# STM32F103C8T6_Minimum_system.net
KiCad netlist of a schematic drawn in Altium Designer
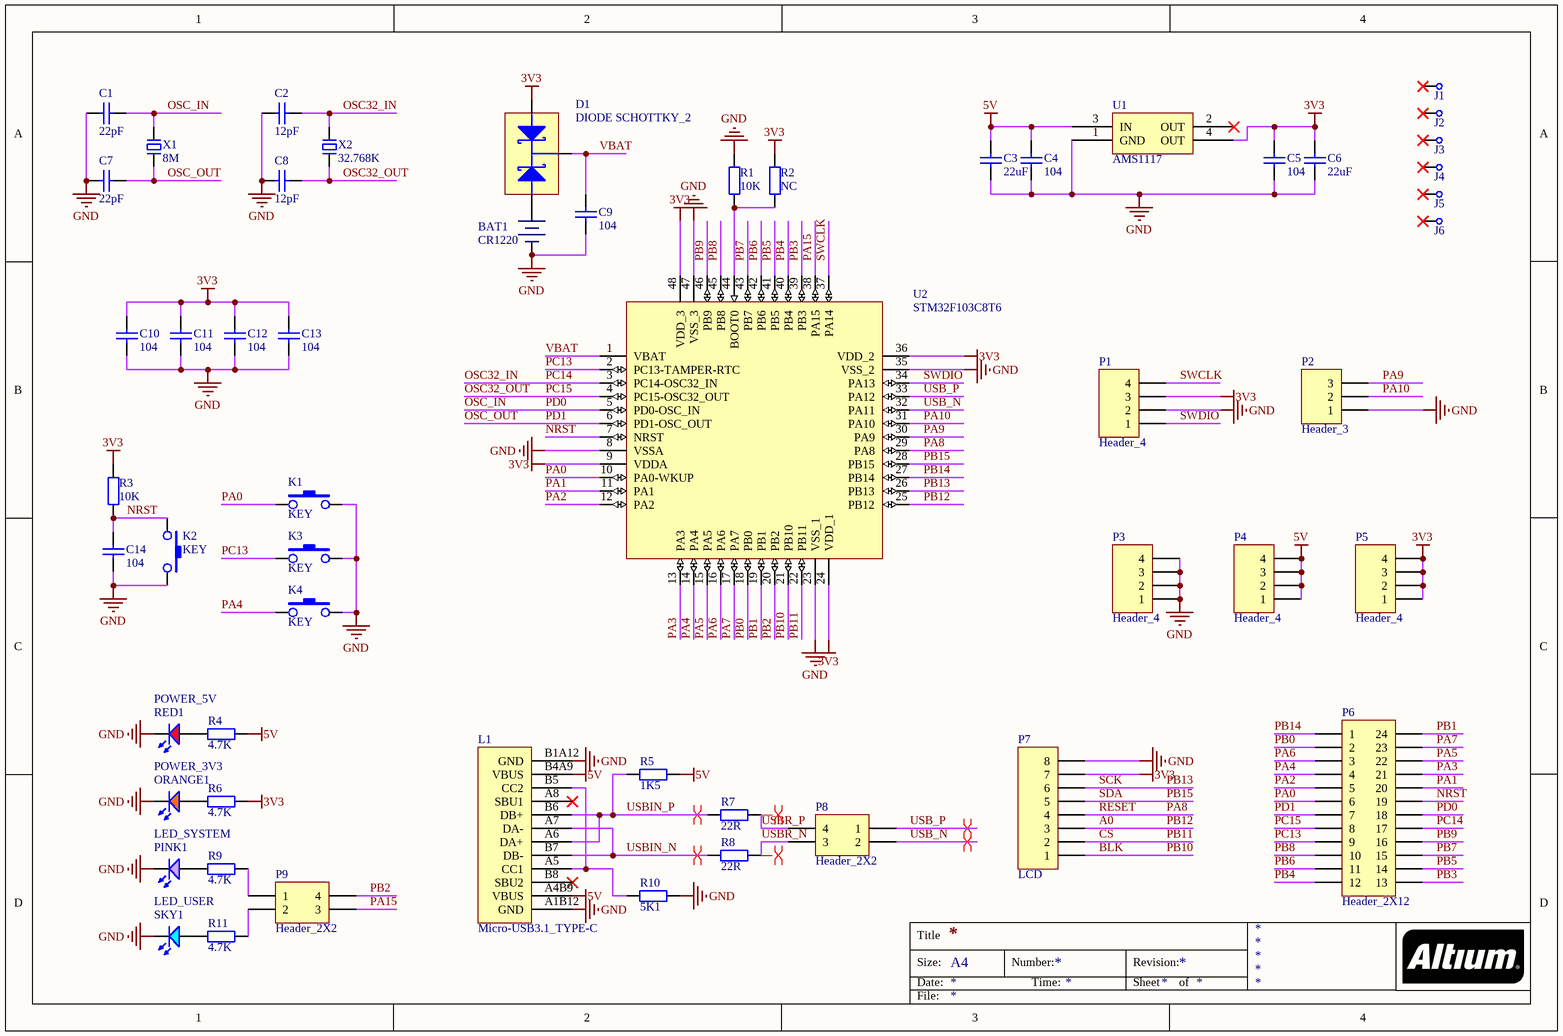
[diagram p0: STM32F103C8T6 Minimum system.SchDoc]

(export (version "E")
  (design (tool "Eeschema 10.0.6"))
  (components
    (comp (ref "BAT1")
      (value "CR1220")
      (footprint "CR1220-B")
      (description "纽扣电池座")
      (libsource (lib "Miscellaneous Socket") (part "CR1220"))
    )
    (comp (ref "C1")
      (value "22pF")
      (footprint "Cap-0603")
      (description "贴片陶瓷电容")
      (libsource (lib "Miscellaneous Base") (part "CAP"))
    )
    (comp (ref "C2")
      (value "12pF")
      (footprint "Cap-0603")
      (description "贴片陶瓷电容")
      (libsource (lib "Miscellaneous Base") (part "CAP"))
    )
    (comp (ref "C3")
      (value "22uF")
      (footprint "Cap-0805")
      (description "贴片陶瓷电容")
      (libsource (lib "Miscellaneous Base") (part "CAP"))
    )
    (comp (ref "C4")
      (value "104")
      (footprint "Cap-0603")
      (description "贴片陶瓷电容")
      (libsource (lib "Miscellaneous Base") (part "CAP"))
    )
    (comp (ref "C5")
      (value "104")
      (footprint "Cap-0603")
      (description "贴片陶瓷电容")
      (libsource (lib "Miscellaneous Base") (part "CAP"))
    )
    (comp (ref "C6")
      (value "22uF")
      (footprint "Cap-0805")
      (description "贴片陶瓷电容")
      (libsource (lib "Miscellaneous Base") (part "CAP"))
    )
    (comp (ref "C7")
      (value "22pF")
      (footprint "Cap-0603")
      (description "贴片陶瓷电容")
      (libsource (lib "Miscellaneous Base") (part "CAP"))
    )
    (comp (ref "C8")
      (value "12pF")
      (footprint "Cap-0603")
      (description "贴片陶瓷电容")
      (libsource (lib "Miscellaneous Base") (part "CAP"))
    )
    (comp (ref "C9")
      (value "104")
      (footprint "Cap-0603")
      (description "贴片陶瓷电容")
      (libsource (lib "Miscellaneous Base") (part "CAP"))
    )
    (comp (ref "C10")
      (value "104")
      (footprint "Cap-0603")
      (description "贴片陶瓷电容")
      (libsource (lib "Miscellaneous Base") (part "CAP"))
    )
    (comp (ref "C11")
      (value "104")
      (footprint "Cap-0603")
      (description "贴片陶瓷电容")
      (libsource (lib "Miscellaneous Base") (part "CAP"))
    )
    (comp (ref "C12")
      (value "104")
      (footprint "Cap-0603")
      (description "贴片陶瓷电容")
      (libsource (lib "Miscellaneous Base") (part "CAP"))
    )
    (comp (ref "C13")
      (value "104")
      (footprint "Cap-0603")
      (description "贴片陶瓷电容")
      (libsource (lib "Miscellaneous Base") (part "CAP"))
    )
    (comp (ref "C14")
      (value "104")
      (footprint "Cap-0603")
      (description "贴片陶瓷电容")
      (libsource (lib "Miscellaneous Base") (part "CAP"))
    )
    (comp (ref "D1")
      (value "DIODE SCHOTTKY_2")
      (footprint "SOT23-3")
      (description "双肖特基二极管")
      (libsource (lib "Miscellaneous Transistor") (part "DIODE SCHOTTKY_2"))
    )
    (comp (ref "J1")
      (value "HOLE_2mm")
      (footprint "HOLE_2mm_1")
      (description "定位孔")
      (libsource (lib "Miscellaneous Others") (part "HOLE_2mm"))
    )
    (comp (ref "J2")
      (value "HOLE_2mm")
      (footprint "HOLE_2mm_1")
      (description "定位孔")
      (libsource (lib "Miscellaneous Others") (part "HOLE_2mm"))
    )
    (comp (ref "J3")
      (value "HOLE_2mm")
      (footprint "HOLE_2mm_1")
      (description "定位孔")
      (libsource (lib "Miscellaneous Others") (part "HOLE_2mm"))
    )
    (comp (ref "J4")
      (value "HOLE_2mm")
      (footprint "HOLE_2mm_1")
      (description "定位孔")
      (libsource (lib "Miscellaneous Others") (part "HOLE_2mm"))
    )
    (comp (ref "J5")
      (value "HOLE_2mm")
      (footprint "HOLE_2mm_1")
      (description "定位孔")
      (libsource (lib "Miscellaneous Others") (part "HOLE_2mm"))
    )
    (comp (ref "J6")
      (value "HOLE_2mm")
      (footprint "HOLE_2mm_1")
      (description "定位孔")
      (libsource (lib "Miscellaneous Others") (part "HOLE_2mm"))
    )
    (comp (ref "K1")
      (value "KEY")
      (footprint "SW-SMD-3X4X2.5")
      (libsource (lib "Miscellaneous Switch") (part "KEY"))
    )
    (comp (ref "K2")
      (value "KEY")
      (footprint "SW-SMD-3X4X2.5")
      (libsource (lib "Miscellaneous Switch") (part "KEY"))
    )
    (comp (ref "K3")
      (value "KEY")
      (footprint "SW-SMD-3X4X2.5")
      (libsource (lib "Miscellaneous Switch") (part "KEY"))
    )
    (comp (ref "K4")
      (value "KEY")
      (footprint "SW-SMD-3X4X2.5")
      (libsource (lib "Miscellaneous Switch") (part "KEY"))
    )
    (comp (ref "L1")
      (value "Micro-USB3.1_TYPE-C")
      (footprint "USB3.0-TYPEC-12P")
      (libsource (lib "Miscellaneous Socket") (part "Micro-USB3.1_TYPE-C"))
    )
    (comp (ref "ORANGE1")
      (value "POWER_3V3")
      (footprint "LED_0603_Y")
      (description "发光二极管")
      (libsource (lib "Miscellaneous Transistor") (part "LED_SMD_ORANGE"))
    )
    (comp (ref "P1")
      (value "Header_4")
      (footprint "Header 2.54X4")
      (libsource (lib "Miscellaneous Header") (part "Header_4"))
    )
    (comp (ref "P2")
      (value "Header_3")
      (footprint "Header 2.54X3")
      (libsource (lib "Miscellaneous Header") (part "Header_3"))
    )
    (comp (ref "P3")
      (value "Header_4")
      (footprint "Header 2.54X4")
      (libsource (lib "Miscellaneous Header") (part "Header_4"))
    )
    (comp (ref "P4")
      (value "Header_4")
      (footprint "Header 2.54X4")
      (libsource (lib "Miscellaneous Header") (part "Header_4"))
    )
    (comp (ref "P5")
      (value "Header_4")
      (footprint "Header 2.54X4")
      (libsource (lib "Miscellaneous Header") (part "Header_4"))
    )
    (comp (ref "P6")
      (value "Header_2X12")
      (footprint "Header 2.54_2X12")
      (libsource (lib "Miscellaneous Header") (part "Header_2X12"))
    )
    (comp (ref "P7")
      (value "LCD")
      (footprint "Header 2.54X8")
      (libsource (lib "Miscellaneous Header") (part "Header_8"))
    )
    (comp (ref "P8")
      (value "Header_2X2")
      (footprint "Header 2.54_2X2")
      (libsource (lib "Miscellaneous Header") (part "Header_2X2"))
    )
    (comp (ref "P9")
      (value "Header_2X2")
      (footprint "Header 2.54_2X2")
      (libsource (lib "") (part "Header_2X2_1"))
    )
    (comp (ref "PINK1")
      (value "LED_SYSTEM")
      (footprint "LED_0603_R")
      (description "发光二极管")
      (libsource (lib "Miscellaneous Transistor") (part "LED_SMD_PINK"))
    )
    (comp (ref "R1")
      (value "10K")
      (footprint "Res-0603")
      (description "贴片电阻")
      (libsource (lib "Miscellaneous Base") (part "RES"))
    )
    (comp (ref "R2")
      (value "NC")
      (footprint "Res-0603")
      (description "贴片电阻")
      (libsource (lib "Miscellaneous Base") (part "RES"))
    )
    (comp (ref "R3")
      (value "10K")
      (footprint "Res-0603")
      (description "贴片电阻")
      (libsource (lib "Miscellaneous Base") (part "RES"))
    )
    (comp (ref "R4")
      (value "4.7K")
      (footprint "Res-0603")
      (description "贴片电阻")
      (libsource (lib "") (part "RES_1"))
    )
    (comp (ref "R5")
      (value "1K5")
      (footprint "Res-0603")
      (description "贴片电阻")
      (libsource (lib "") (part "RES_2"))
    )
    (comp (ref "R6")
      (value "4.7K")
      (footprint "Res-0603")
      (description "贴片电阻")
      (libsource (lib "") (part "RES_1"))
    )
    (comp (ref "R7")
      (value "22R")
      (footprint "Res-0603")
      (description "贴片电阻")
      (libsource (lib "") (part "RES_2"))
    )
    (comp (ref "R8")
      (value "22R")
      (footprint "Res-0603")
      (description "贴片电阻")
      (libsource (lib "") (part "RES_2"))
    )
    (comp (ref "R9")
      (value "4.7K")
      (footprint "Res-0603")
      (description "贴片电阻")
      (libsource (lib "") (part "RES_1"))
    )
    (comp (ref "R10")
      (value "5K1")
      (footprint "Res-0603")
      (description "贴片电阻")
      (libsource (lib "") (part "RES_2"))
    )
    (comp (ref "R11")
      (value "4.7K")
      (footprint "Res-0603")
      (description "贴片电阻")
      (libsource (lib "") (part "RES_1"))
    )
    (comp (ref "RED1")
      (value "POWER_5V")
      (footprint "LED_0603_R")
      (description "发光二极管")
      (libsource (lib "Miscellaneous Transistor") (part "LED_SMD_RED"))
    )
    (comp (ref "SKY1")
      (value "LED_USER")
      (footprint "LED_0603_B")
      (description "发光二极管")
      (libsource (lib "Miscellaneous Transistor") (part "LED_SMD_BLUE_SKY"))
    )
    (comp (ref "U1")
      (value "AMS1117")
      (footprint "AMS1117")
      (libsource (lib "Miscellaneous PMIC") (part "AMS1117"))
    )
    (comp (ref "U2")
      (value "STM32F103C8T6")
      (footprint "STM32F103C8T6")
      (libsource (lib "Miscellaneous MCU") (part "STM32F103C8T6"))
    )
    (comp (ref "X1")
      (value "8M")
      (footprint "OSC 5032-2P")
      (description "2脚无源脚晶振")
      (libsource (lib "Miscellaneous XTAL") (part "XTAL-2P"))
    )
    (comp (ref "X2")
      (value "32.768K")
      (footprint "OSC 3215-2P")
      (description "2脚无源脚晶振")
      (libsource (lib "Miscellaneous XTAL") (part "XTAL-2P"))
    )
  )
  (nets
    (net (code "1") (name "/A0") (class "Default")
      (node (ref "P7") (pin "3") (pinfunction "3_3") (pintype "passive"))
      (node (ref "U2") (pin "25") (pinfunction "PB12_25") (pintype "bidirectional"))
    )
    (net (code "2") (name "/BLK") (class "Default")
      (node (ref "P7") (pin "1") (pinfunction "1_1") (pintype "passive"))
      (node (ref "U2") (pin "21") (pinfunction "PB10_21") (pintype "bidirectional"))
    )
    (net (code "3") (name "/CS") (class "Default")
      (node (ref "P7") (pin "2") (pinfunction "2_2") (pintype "passive"))
      (node (ref "U2") (pin "22") (pinfunction "PB11_22") (pintype "bidirectional"))
    )
    (net (code "4") (name "/NRST") (class "Default")
      (node (ref "C14") (pin "2") (pinfunction "2_2") (pintype "passive"))
      (node (ref "K2") (pin "1") (pinfunction "1_1") (pintype "passive"))
      (node (ref "P6") (pin "19") (pinfunction "19_19") (pintype "power_in"))
      (node (ref "R3") (pin "1") (pinfunction "1_1") (pintype "passive"))
      (node (ref "U2") (pin "7") (pinfunction "NRST_7") (pintype "bidirectional"))
    )
    (net (code "5") (name "/OSC32_IN") (class "Default")
      (node (ref "C2") (pin "2") (pinfunction "2_2") (pintype "passive"))
      (node (ref "P6") (pin "17") (pinfunction "17_17") (pintype "power_in"))
      (node (ref "U2") (pin "3") (pinfunction "PC14-OSC32_IN_3") (pintype "bidirectional"))
      (node (ref "X2") (pin "2") (pinfunction "2_2") (pintype "passive"))
    )
    (net (code "6") (name "/OSC32_OUT") (class "Default")
      (node (ref "C8") (pin "2") (pinfunction "2_2") (pintype "passive"))
      (node (ref "P6") (pin "8") (pinfunction "8_8") (pintype "power_in"))
      (node (ref "U2") (pin "4") (pinfunction "PC15-OSC32_OUT_4") (pintype "bidirectional"))
      (node (ref "X2") (pin "1") (pinfunction "1_1") (pintype "passive"))
    )
    (net (code "7") (name "/OSC_IN") (class "Default")
      (node (ref "C1") (pin "2") (pinfunction "2_2") (pintype "passive"))
      (node (ref "P6") (pin "18") (pinfunction "18_18") (pintype "power_in"))
      (node (ref "U2") (pin "5") (pinfunction "PD0-OSC_IN_5") (pintype "bidirectional"))
      (node (ref "X1") (pin "2") (pinfunction "2_2") (pintype "passive"))
    )
    (net (code "8") (name "/OSC_OUT") (class "Default")
      (node (ref "C7") (pin "2") (pinfunction "2_2") (pintype "passive"))
      (node (ref "P6") (pin "7") (pinfunction "7_7") (pintype "power_in"))
      (node (ref "U2") (pin "6") (pinfunction "PD1-OSC_OUT_6") (pintype "bidirectional"))
      (node (ref "X1") (pin "1") (pinfunction "1_1") (pintype "passive"))
    )
    (net (code "9") (name "/PA0") (class "Default")
      (node (ref "K1") (pin "1") (pinfunction "1_1") (pintype "passive"))
      (node (ref "P6") (pin "6") (pinfunction "6_6") (pintype "power_in"))
      (node (ref "U2") (pin "10") (pinfunction "PA0-WKUP_10") (pintype "bidirectional"))
    )
    (net (code "10") (name "/PA1") (class "Default")
      (node (ref "P6") (pin "20") (pinfunction "20_20") (pintype "power_in"))
      (node (ref "U2") (pin "11") (pinfunction "PA1_11") (pintype "bidirectional"))
    )
    (net (code "11") (name "/PA2") (class "Default")
      (node (ref "P6") (pin "5") (pinfunction "5_5") (pintype "power_in"))
      (node (ref "U2") (pin "12") (pinfunction "PA2_12") (pintype "bidirectional"))
    )
    (net (code "12") (name "/PA3") (class "Default")
      (node (ref "P6") (pin "21") (pinfunction "21_21") (pintype "power_in"))
      (node (ref "U2") (pin "13") (pinfunction "PA3_13") (pintype "bidirectional"))
    )
    (net (code "13") (name "/PA4") (class "Default")
      (node (ref "K4") (pin "1") (pinfunction "1_1") (pintype "passive"))
      (node (ref "P6") (pin "4") (pinfunction "4_4") (pintype "power_in"))
      (node (ref "U2") (pin "14") (pinfunction "PA4_14") (pintype "bidirectional"))
    )
    (net (code "14") (name "/PA5") (class "Default")
      (node (ref "P6") (pin "22") (pinfunction "22_22") (pintype "power_in"))
      (node (ref "U2") (pin "15") (pinfunction "PA5_15") (pintype "bidirectional"))
    )
    (net (code "15") (name "/PA6") (class "Default")
      (node (ref "P6") (pin "3") (pinfunction "3_3") (pintype "power_in"))
      (node (ref "U2") (pin "16") (pinfunction "PA6_16") (pintype "bidirectional"))
    )
    (net (code "16") (name "/PA7") (class "Default")
      (node (ref "P6") (pin "23") (pinfunction "23_23") (pintype "power_in"))
      (node (ref "U2") (pin "17") (pinfunction "PA7_17") (pintype "bidirectional"))
    )
    (net (code "17") (name "/PA8") (class "Default")
      (node (ref "P7") (pin "4") (pinfunction "4_4") (pintype "passive"))
      (node (ref "U2") (pin "29") (pinfunction "PA8_29") (pintype "bidirectional"))
    )
    (net (code "18") (name "/PA9") (class "Default")
      (node (ref "P2") (pin "3") (pinfunction "3_3") (pintype "passive"))
      (node (ref "U2") (pin "30") (pinfunction "PA9_30") (pintype "bidirectional"))
    )
    (net (code "19") (name "/PA10") (class "Default")
      (node (ref "P2") (pin "2") (pinfunction "2_2") (pintype "passive"))
      (node (ref "U2") (pin "31") (pinfunction "PA10_31") (pintype "bidirectional"))
    )
    (net (code "20") (name "/PA15") (class "Default")
      (node (ref "P9") (pin "3") (pinfunction "3_3") (pintype "passive"))
      (node (ref "U2") (pin "38") (pinfunction "PA15_38") (pintype "bidirectional"))
    )
    (net (code "21") (name "/PB0") (class "Default")
      (node (ref "P6") (pin "2") (pinfunction "2_2") (pintype "power_in"))
      (node (ref "U2") (pin "18") (pinfunction "PB0_18") (pintype "bidirectional"))
    )
    (net (code "22") (name "/PB1") (class "Default")
      (node (ref "P6") (pin "24") (pinfunction "24_24") (pintype "power_in"))
      (node (ref "U2") (pin "19") (pinfunction "PB1_19") (pintype "bidirectional"))
    )
    (net (code "23") (name "/PB2") (class "Default")
      (node (ref "P9") (pin "4") (pinfunction "4_4") (pintype "passive"))
      (node (ref "U2") (pin "20") (pinfunction "PB2_20") (pintype "bidirectional"))
    )
    (net (code "24") (name "/PB3") (class "Default")
      (node (ref "P6") (pin "13") (pinfunction "13_13") (pintype "power_in"))
      (node (ref "U2") (pin "39") (pinfunction "PB3_39") (pintype "bidirectional"))
    )
    (net (code "25") (name "/PB4") (class "Default")
      (node (ref "P6") (pin "12") (pinfunction "12_12") (pintype "power_in"))
      (node (ref "U2") (pin "40") (pinfunction "PB4_40") (pintype "bidirectional"))
    )
    (net (code "26") (name "/PB5") (class "Default")
      (node (ref "P6") (pin "14") (pinfunction "14_14") (pintype "power_in"))
      (node (ref "U2") (pin "41") (pinfunction "PB5_41") (pintype "bidirectional"))
    )
    (net (code "27") (name "/PB6") (class "Default")
      (node (ref "P6") (pin "11") (pinfunction "11_11") (pintype "power_in"))
      (node (ref "U2") (pin "42") (pinfunction "PB6_42") (pintype "bidirectional"))
    )
    (net (code "28") (name "/PB7") (class "Default")
      (node (ref "P6") (pin "15") (pinfunction "15_15") (pintype "power_in"))
      (node (ref "U2") (pin "43") (pinfunction "PB7_43") (pintype "bidirectional"))
    )
    (net (code "29") (name "/PB8") (class "Default")
      (node (ref "P6") (pin "10") (pinfunction "10_10") (pintype "power_in"))
      (node (ref "U2") (pin "45") (pinfunction "PB8_45") (pintype "bidirectional"))
    )
    (net (code "30") (name "/PB9") (class "Default")
      (node (ref "P6") (pin "16") (pinfunction "16_16") (pintype "power_in"))
      (node (ref "U2") (pin "46") (pinfunction "PB9_46") (pintype "bidirectional"))
    )
    (net (code "31") (name "/PB13") (class "Default")
      (node (ref "P7") (pin "6") (pinfunction "6_6") (pintype "passive"))
      (node (ref "U2") (pin "26") (pinfunction "PB13_26") (pintype "bidirectional"))
    )
    (net (code "32") (name "/PB14") (class "Default")
      (node (ref "P6") (pin "1") (pinfunction "1_1") (pintype "power_in"))
      (node (ref "U2") (pin "27") (pinfunction "PB14_27") (pintype "bidirectional"))
    )
    (net (code "33") (name "/PB15") (class "Default")
      (node (ref "P7") (pin "5") (pinfunction "5_5") (pintype "passive"))
      (node (ref "U2") (pin "28") (pinfunction "PB15_28") (pintype "bidirectional"))
    )
    (net (code "34") (name "/PC13") (class "Default")
      (node (ref "K3") (pin "1") (pinfunction "1_1") (pintype "passive"))
      (node (ref "P6") (pin "9") (pinfunction "9_9") (pintype "power_in"))
      (node (ref "U2") (pin "2") (pinfunction "PC13-TAMPER-RTC_2") (pintype "bidirectional"))
    )
    (net (code "35") (name "/SWCLK") (class "Default")
      (node (ref "P1") (pin "4") (pinfunction "4_4") (pintype "passive"))
      (node (ref "U2") (pin "37") (pinfunction "PA14_37") (pintype "bidirectional"))
    )
    (net (code "36") (name "/SWDIO") (class "Default")
      (node (ref "P1") (pin "1") (pinfunction "1_1") (pintype "passive"))
      (node (ref "U2") (pin "34") (pinfunction "PA13_34") (pintype "bidirectional"))
    )
    (net (code "37") (name "/USBIN_N") (class "Default")
      (node (ref "L1") (pin "A7") (pinfunction "DA-_A7") (pintype "passive"))
      (node (ref "L1") (pin "B7") (pinfunction "DB-_B7") (pintype "passive"))
      (node (ref "R8") (pin "2") (pinfunction "2_2") (pintype "passive"))
    )
    (net (code "38") (name "/USBIN_P") (class "Default")
      (node (ref "L1") (pin "A6") (pinfunction "DA+_A6") (pintype "passive"))
      (node (ref "L1") (pin "B6") (pinfunction "DB+_B6") (pintype "passive"))
      (node (ref "R5") (pin "2") (pinfunction "2_2") (pintype "passive"))
      (node (ref "R7") (pin "2") (pinfunction "2_2") (pintype "passive"))
    )
    (net (code "39") (name "/USBR_N") (class "Default")
      (node (ref "P8") (pin "3") (pinfunction "3_3") (pintype "passive"))
      (node (ref "R8") (pin "1") (pinfunction "1_1") (pintype "passive"))
    )
    (net (code "40") (name "/USBR_P") (class "Default")
      (node (ref "P8") (pin "4") (pinfunction "4_4") (pintype "passive"))
      (node (ref "R7") (pin "1") (pinfunction "1_1") (pintype "passive"))
    )
    (net (code "41") (name "/USB_N") (class "Default")
      (node (ref "P8") (pin "2") (pinfunction "2_2") (pintype "passive"))
      (node (ref "U2") (pin "32") (pinfunction "PA11_32") (pintype "bidirectional"))
    )
    (net (code "42") (name "/USB_P") (class "Default")
      (node (ref "P8") (pin "1") (pinfunction "1_1") (pintype "passive"))
      (node (ref "U2") (pin "33") (pinfunction "PA12_33") (pintype "bidirectional"))
    )
    (net (code "43") (name "/VBAT") (class "Default")
      (node (ref "C9") (pin "2") (pinfunction "2_2") (pintype "passive"))
      (node (ref "D1") (pin "3") (pinfunction "3_3") (pintype "passive"))
      (node (ref "U2") (pin "1") (pinfunction "VBAT_1") (pintype "power_in"))
    )
    (net (code "44") (name "3V3") (class "Default")
      (node (ref "C10") (pin "2") (pinfunction "2_2") (pintype "passive"))
      (node (ref "C11") (pin "2") (pinfunction "2_2") (pintype "passive"))
      (node (ref "C12") (pin "2") (pinfunction "2_2") (pintype "passive"))
      (node (ref "C13") (pin "2") (pinfunction "2_2") (pintype "passive"))
      (node (ref "C5") (pin "2") (pinfunction "2_2") (pintype "passive"))
      (node (ref "C6") (pin "2") (pinfunction "2_2") (pintype "passive"))
      (node (ref "D1") (pin "1") (pinfunction "1_1") (pintype "passive"))
      (node (ref "P1") (pin "3") (pinfunction "3_3") (pintype "passive"))
      (node (ref "P5") (pin "1") (pinfunction "1_1") (pintype "passive"))
      (node (ref "P5") (pin "2") (pinfunction "2_2") (pintype "passive"))
      (node (ref "P5") (pin "3") (pinfunction "3_3") (pintype "passive"))
      (node (ref "P5") (pin "4") (pinfunction "4_4") (pintype "passive"))
      (node (ref "P7") (pin "7") (pinfunction "7_7") (pintype "passive"))
      (node (ref "R2") (pin "2") (pinfunction "2_2") (pintype "passive"))
      (node (ref "R3") (pin "2") (pinfunction "2_2") (pintype "passive"))
      (node (ref "R6") (pin "2") (pinfunction "2_2") (pintype "passive"))
      (node (ref "U1") (pin "4") (pinfunction "OUT_4") (pintype "passive"))
      (node (ref "U2") (pin "24") (pinfunction "VDD_1_24") (pintype "power_in"))
      (node (ref "U2") (pin "36") (pinfunction "VDD_2_36") (pintype "power_in"))
      (node (ref "U2") (pin "48") (pinfunction "VDD_3_48") (pintype "power_in"))
      (node (ref "U2") (pin "9") (pinfunction "VDDA_9") (pintype "power_in"))
    )
    (net (code "45") (name "5V") (class "Default")
      (node (ref "C3") (pin "2") (pinfunction "2_2") (pintype "passive"))
      (node (ref "C4") (pin "2") (pinfunction "2_2") (pintype "passive"))
      (node (ref "L1") (pin "A4B9") (pinfunction "VBUS_A4B9") (pintype "passive"))
      (node (ref "L1") (pin "B4A9") (pinfunction "VBUS_B4A9") (pintype "passive"))
      (node (ref "P4") (pin "1") (pinfunction "1_1") (pintype "passive"))
      (node (ref "P4") (pin "2") (pinfunction "2_2") (pintype "passive"))
      (node (ref "P4") (pin "3") (pinfunction "3_3") (pintype "passive"))
      (node (ref "P4") (pin "4") (pinfunction "4_4") (pintype "passive"))
      (node (ref "R4") (pin "2") (pinfunction "2_2") (pintype "passive"))
      (node (ref "R5") (pin "1") (pinfunction "1_1") (pintype "passive"))
      (node (ref "U1") (pin "3") (pinfunction "IN_3") (pintype "passive"))
    )
    (net (code "46") (name "GND") (class "Default")
      (node (ref "BAT1") (pin "2") (pinfunction "2_2") (pintype "passive"))
      (node (ref "C1") (pin "1") (pinfunction "1_1") (pintype "passive"))
      (node (ref "C10") (pin "1") (pinfunction "1_1") (pintype "passive"))
      (node (ref "C11") (pin "1") (pinfunction "1_1") (pintype "passive"))
      (node (ref "C12") (pin "1") (pinfunction "1_1") (pintype "passive"))
      (node (ref "C13") (pin "1") (pinfunction "1_1") (pintype "passive"))
      (node (ref "C14") (pin "1") (pinfunction "1_1") (pintype "passive"))
      (node (ref "C2") (pin "1") (pinfunction "1_1") (pintype "passive"))
      (node (ref "C3") (pin "1") (pinfunction "1_1") (pintype "passive"))
      (node (ref "C4") (pin "1") (pinfunction "1_1") (pintype "passive"))
      (node (ref "C5") (pin "1") (pinfunction "1_1") (pintype "passive"))
      (node (ref "C6") (pin "1") (pinfunction "1_1") (pintype "passive"))
      (node (ref "C7") (pin "1") (pinfunction "1_1") (pintype "passive"))
      (node (ref "C8") (pin "1") (pinfunction "1_1") (pintype "passive"))
      (node (ref "C9") (pin "1") (pinfunction "1_1") (pintype "passive"))
      (node (ref "K1") (pin "3") (pinfunction "3_3") (pintype "passive"))
      (node (ref "K2") (pin "3") (pinfunction "3_3") (pintype "passive"))
      (node (ref "K3") (pin "3") (pinfunction "3_3") (pintype "passive"))
      (node (ref "K4") (pin "3") (pinfunction "3_3") (pintype "passive"))
      (node (ref "L1") (pin "A1B12") (pinfunction "GND_A1B12") (pintype "passive"))
      (node (ref "L1") (pin "B1A12") (pinfunction "GND_B1A12") (pintype "passive"))
      (node (ref "ORANGE1") (pin "2") (pinfunction "K_2") (pintype "passive"))
      (node (ref "P1") (pin "2") (pinfunction "2_2") (pintype "passive"))
      (node (ref "P2") (pin "1") (pinfunction "1_1") (pintype "passive"))
      (node (ref "P3") (pin "1") (pinfunction "1_1") (pintype "passive"))
      (node (ref "P3") (pin "2") (pinfunction "2_2") (pintype "passive"))
      (node (ref "P3") (pin "3") (pinfunction "3_3") (pintype "passive"))
      (node (ref "P3") (pin "4") (pinfunction "4_4") (pintype "passive"))
      (node (ref "P7") (pin "8") (pinfunction "8_8") (pintype "passive"))
      (node (ref "PINK1") (pin "2") (pinfunction "K_2") (pintype "passive"))
      (node (ref "R1") (pin "2") (pinfunction "2_2") (pintype "passive"))
      (node (ref "R10") (pin "1") (pinfunction "1_1") (pintype "passive"))
      (node (ref "RED1") (pin "2") (pinfunction "K_2") (pintype "passive"))
      (node (ref "SKY1") (pin "2") (pinfunction "K_2") (pintype "passive"))
      (node (ref "U1") (pin "1") (pinfunction "GND_1") (pintype "passive"))
      (node (ref "U2") (pin "23") (pinfunction "VSS_1_23") (pintype "power_in"))
      (node (ref "U2") (pin "35") (pinfunction "VSS_2_35") (pintype "power_in"))
      (node (ref "U2") (pin "47") (pinfunction "VSS_3_47") (pintype "power_in"))
      (node (ref "U2") (pin "8") (pinfunction "VSSA_8") (pintype "power_in"))
    )
    (net (code "47") (name "Net-(BAT1-Pad1)") (class "Default")
      (node (ref "BAT1") (pin "1") (pinfunction "1_1") (pintype "passive"))
      (node (ref "D1") (pin "2") (pinfunction "2_2") (pintype "passive"))
    )
    (net (code "48") (name "Net-(L1-CC1)") (class "Default")
      (node (ref "L1") (pin "A5") (pinfunction "CC1_A5") (pintype "passive"))
      (node (ref "L1") (pin "B5") (pinfunction "CC2_B5") (pintype "passive"))
      (node (ref "R10") (pin "2") (pinfunction "2_2") (pintype "passive"))
    )
    (net (code "49") (name "Net-(ORANGE1-A)") (class "Default")
      (node (ref "ORANGE1") (pin "1") (pinfunction "A_1") (pintype "passive"))
      (node (ref "R6") (pin "1") (pinfunction "1_1") (pintype "passive"))
    )
    (net (code "50") (name "Net-(P9-Pad1)") (class "Default")
      (node (ref "P9") (pin "1") (pinfunction "1_1") (pintype "passive"))
      (node (ref "R9") (pin "2") (pinfunction "2_2") (pintype "passive"))
    )
    (net (code "51") (name "Net-(P9-Pad2)") (class "Default")
      (node (ref "P9") (pin "2") (pinfunction "2_2") (pintype "passive"))
      (node (ref "R11") (pin "2") (pinfunction "2_2") (pintype "passive"))
    )
    (net (code "52") (name "Net-(PINK1-A)") (class "Default")
      (node (ref "PINK1") (pin "1") (pinfunction "A_1") (pintype "passive"))
      (node (ref "R9") (pin "1") (pinfunction "1_1") (pintype "passive"))
    )
    (net (code "53") (name "Net-(RED1-A)") (class "Default")
      (node (ref "R4") (pin "1") (pinfunction "1_1") (pintype "passive"))
      (node (ref "RED1") (pin "1") (pinfunction "A_1") (pintype "passive"))
    )
    (net (code "54") (name "Net-(SKY1-A)") (class "Default")
      (node (ref "R11") (pin "1") (pinfunction "1_1") (pintype "passive"))
      (node (ref "SKY1") (pin "1") (pinfunction "A_1") (pintype "passive"))
    )
    (net (code "55") (name "Net-(U2-BOOT0)") (class "Default")
      (node (ref "R1") (pin "1") (pinfunction "1_1") (pintype "passive"))
      (node (ref "R2") (pin "1") (pinfunction "1_1") (pintype "passive"))
      (node (ref "U2") (pin "44") (pinfunction "BOOT0_44") (pintype "input"))
    )
    (net (code "56") (name "unconnected-(J1-Pad1)") (class "Default")
      (node (ref "J1") (pin "1") (pinfunction "1_1") (pintype "passive+no_connect"))
    )
    (net (code "57") (name "unconnected-(J2-Pad1)") (class "Default")
      (node (ref "J2") (pin "1") (pinfunction "1_1") (pintype "passive+no_connect"))
    )
    (net (code "58") (name "unconnected-(J3-Pad1)") (class "Default")
      (node (ref "J3") (pin "1") (pinfunction "1_1") (pintype "passive+no_connect"))
    )
    (net (code "59") (name "unconnected-(J4-Pad1)") (class "Default")
      (node (ref "J4") (pin "1") (pinfunction "1_1") (pintype "passive+no_connect"))
    )
    (net (code "60") (name "unconnected-(J5-Pad1)") (class "Default")
      (node (ref "J5") (pin "1") (pinfunction "1_1") (pintype "passive+no_connect"))
    )
    (net (code "61") (name "unconnected-(J6-Pad1)") (class "Default")
      (node (ref "J6") (pin "1") (pinfunction "1_1") (pintype "passive+no_connect"))
    )
    (net (code "62") (name "unconnected-(L1-SBU1-PadA8)") (class "Default")
      (node (ref "L1") (pin "A8") (pinfunction "SBU1_A8") (pintype "passive+no_connect"))
    )
    (net (code "63") (name "unconnected-(L1-SBU2-PadB8)") (class "Default")
      (node (ref "L1") (pin "B8") (pinfunction "SBU2_B8") (pintype "passive+no_connect"))
    )
    (net (code "64") (name "unconnected-(U1-OUT-Pad2)") (class "Default")
      (node (ref "U1") (pin "2") (pinfunction "OUT_2") (pintype "passive+no_connect"))
    )
  )
)
